# Vector_XY_Driver.net
KiCad netlist of a schematic drawn in EAGLE
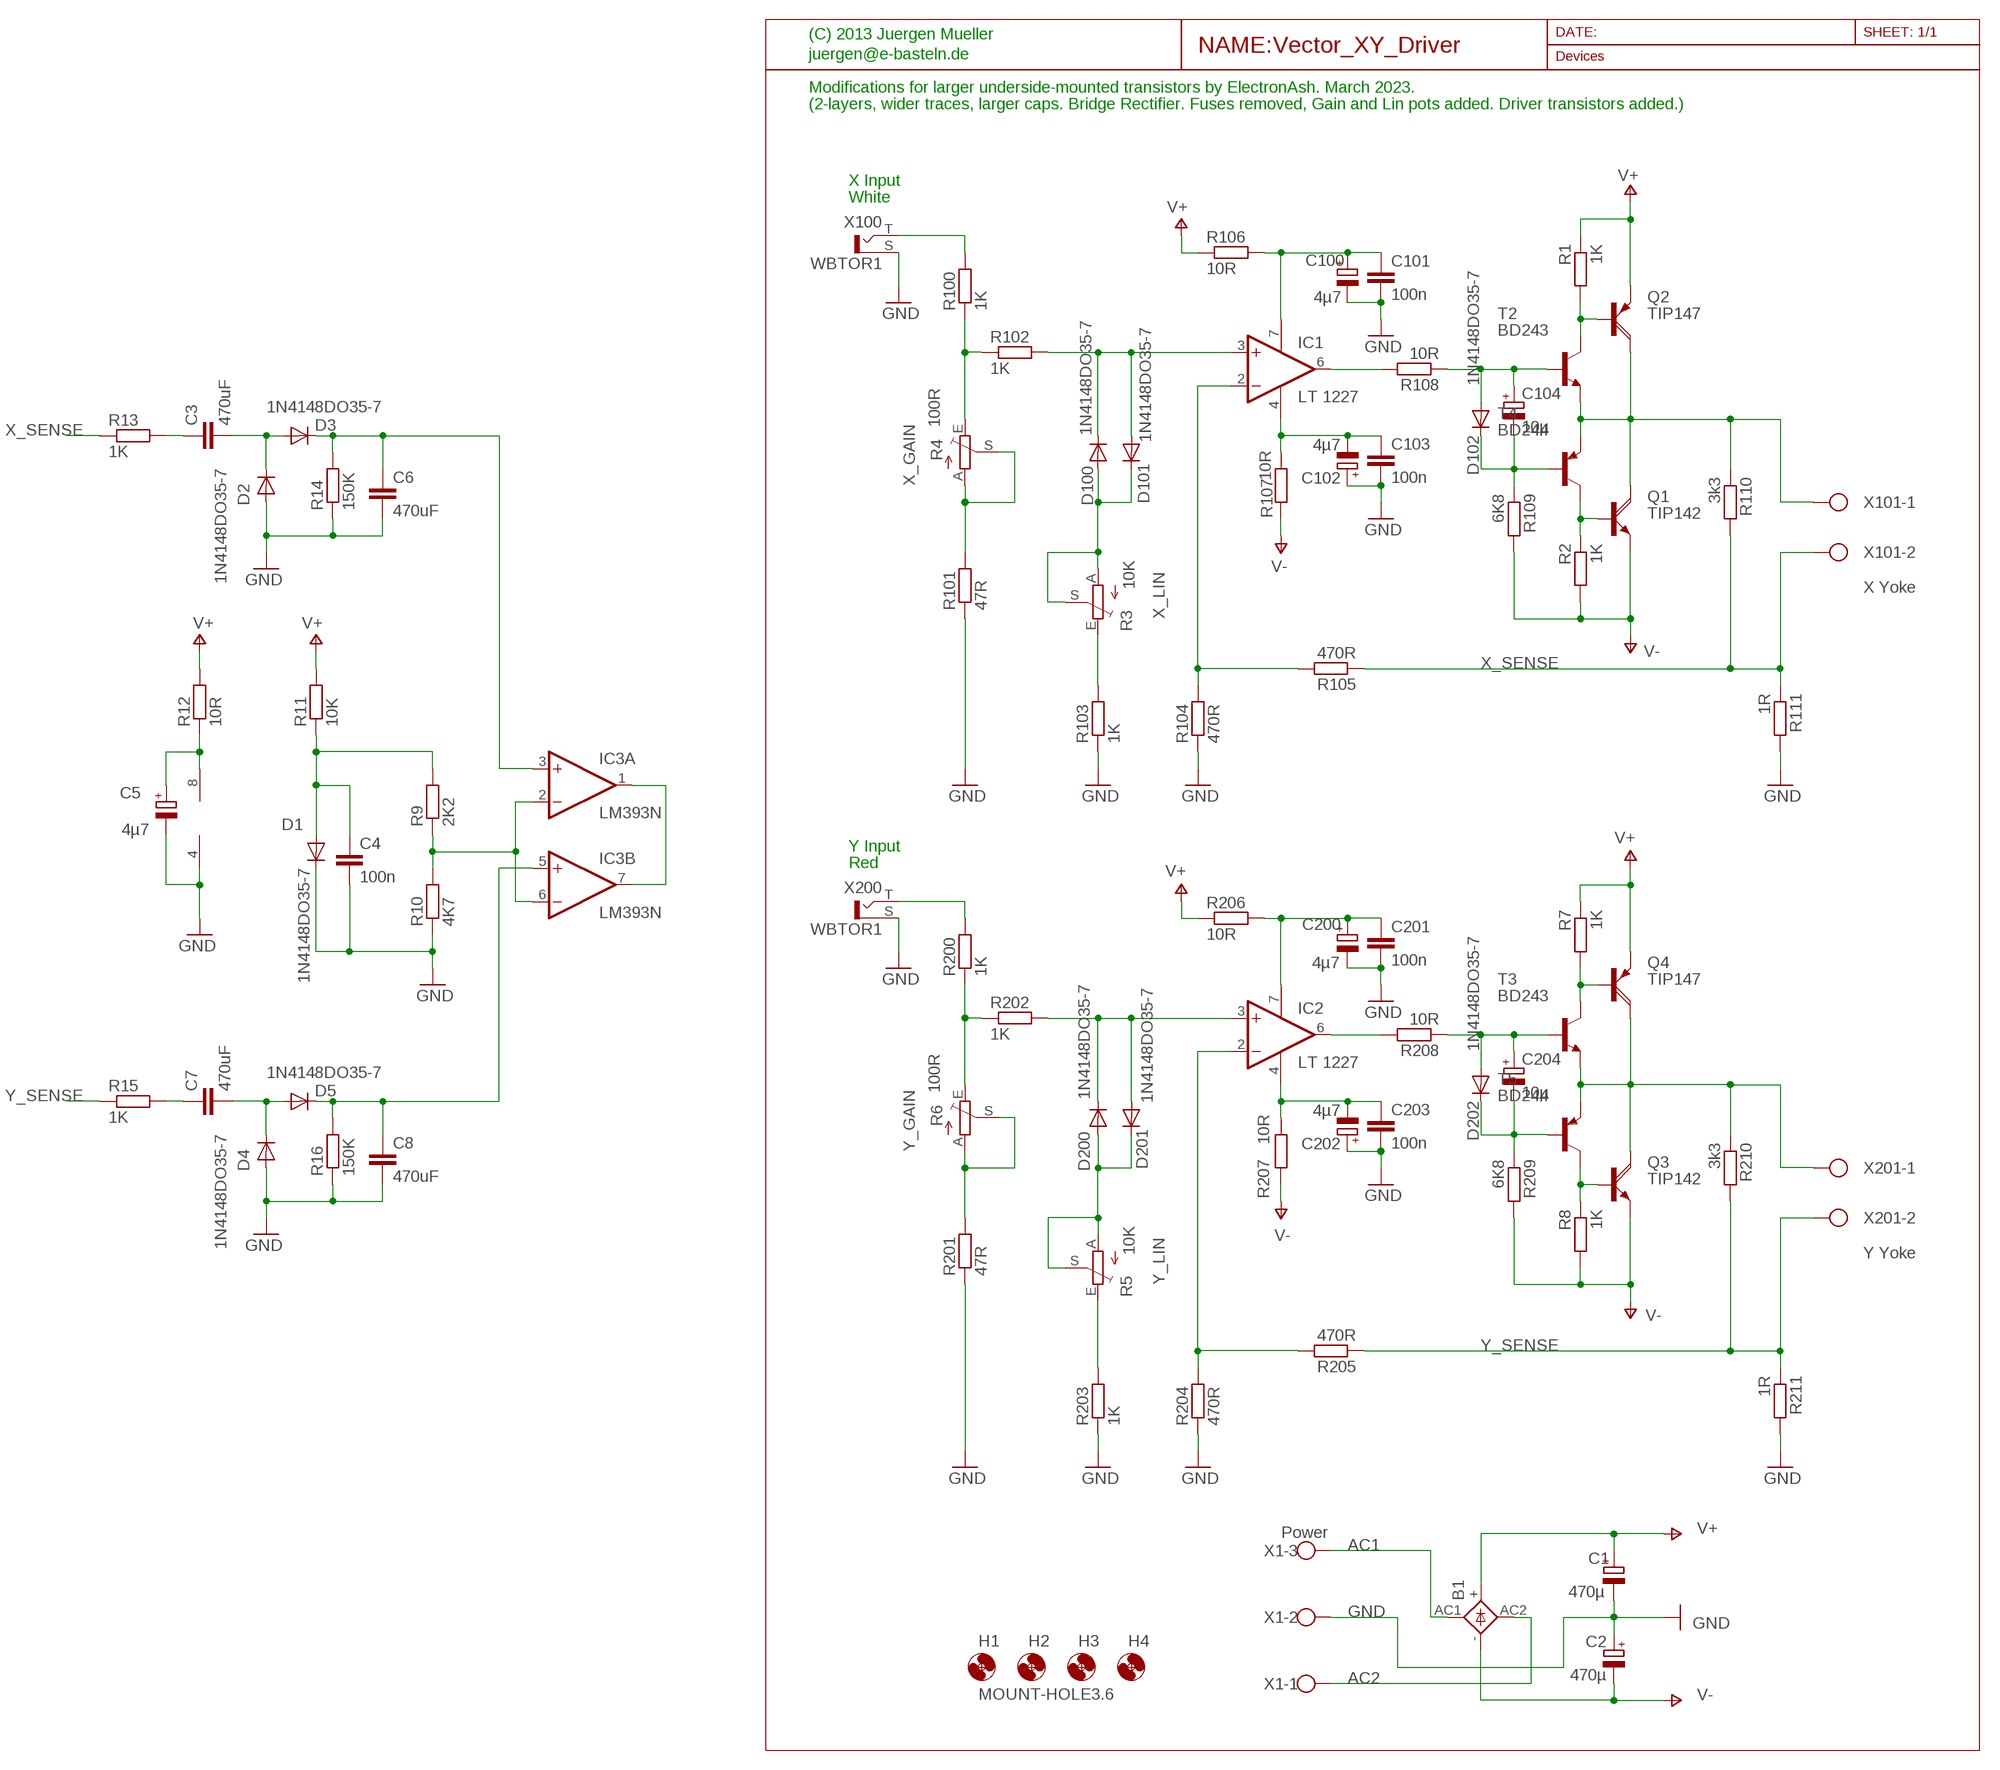
[diagram p0: schematic, sheet 1]

(export (version "E")
  (design (tool "Eeschema 10.0.6"))
  (components
    (comp (ref "B1")
      (value "2KBP")
      (footprint "eagle-import:2KBP")
      (libsource (lib "eagle-import") (part "2KBP"))
    )
    (comp (ref "C1")
      (value "470µ")
      (footprint "eagle-import:E7,5-16")
      (libsource (lib "eagle-import") (part "CPOL-EUE7.5-16"))
    )
    (comp (ref "C2")
      (value "470µ")
      (footprint "eagle-import:E7,5-16")
      (libsource (lib "eagle-import") (part "CPOL-EUE7.5-16"))
    )
    (comp (ref "C3")
      (value "470uF")
      (footprint "eagle-import:C025_050-025X075")
      (libsource (lib "eagle-import") (part "C-EU025_050-025X075"))
    )
    (comp (ref "C4")
      (value "100n")
      (footprint "eagle-import:C025_050-025X075")
      (libsource (lib "eagle-import") (part "C-EU025_050-025X075"))
    )
    (comp (ref "C5")
      (value "4µ7")
      (footprint "eagle-import:E2,5-6")
      (libsource (lib "eagle-import") (part "CPOL-EUE2.5-6"))
    )
    (comp (ref "C6")
      (value "470uF")
      (footprint "eagle-import:C025_050-025X075")
      (libsource (lib "eagle-import") (part "C-EU025_050-025X075"))
    )
    (comp (ref "C7")
      (value "470uF")
      (footprint "eagle-import:C025_050-025X075")
      (libsource (lib "eagle-import") (part "C-EU025_050-025X075"))
    )
    (comp (ref "C8")
      (value "470uF")
      (footprint "eagle-import:C025_050-025X075")
      (libsource (lib "eagle-import") (part "C-EU025_050-025X075"))
    )
    (comp (ref "C100")
      (value "4µ7")
      (footprint "eagle-import:E2,5-6")
      (libsource (lib "eagle-import") (part "CPOL-EUE2.5-6"))
    )
    (comp (ref "C101")
      (value "100n")
      (footprint "eagle-import:C025_050-025X075")
      (libsource (lib "eagle-import") (part "C-EU025_050-025X075"))
    )
    (comp (ref "C102")
      (value "4µ7")
      (footprint "eagle-import:E2,5-6")
      (libsource (lib "eagle-import") (part "CPOL-EUE2.5-6"))
    )
    (comp (ref "C103")
      (value "100n")
      (footprint "eagle-import:C025_050-025X075")
      (libsource (lib "eagle-import") (part "C-EU025_050-025X075"))
    )
    (comp (ref "C104")
      (value "10µ")
      (footprint "eagle-import:E15-5")
      (libsource (lib "eagle-import") (part "CPOL-EUE15-5AXIAL"))
    )
    (comp (ref "C200")
      (value "4µ7")
      (footprint "eagle-import:E2,5-6")
      (libsource (lib "eagle-import") (part "CPOL-EUE2.5-6"))
    )
    (comp (ref "C201")
      (value "100n")
      (footprint "eagle-import:C025_050-025X075")
      (libsource (lib "eagle-import") (part "C-EU025_050-025X075"))
    )
    (comp (ref "C202")
      (value "4µ7")
      (footprint "eagle-import:E2,5-6")
      (libsource (lib "eagle-import") (part "CPOL-EUE2.5-6"))
    )
    (comp (ref "C203")
      (value "100n")
      (footprint "eagle-import:C025_050-025X075")
      (libsource (lib "eagle-import") (part "C-EU025_050-025X075"))
    )
    (comp (ref "C204")
      (value "10µ")
      (footprint "eagle-import:E15-5")
      (libsource (lib "eagle-import") (part "CPOL-EUE15-5AXIAL"))
    )
    (comp (ref "D1")
      (value "1N4148DO35-7")
      (footprint "eagle-import:DO35-7")
      (libsource (lib "eagle-import") (part "1N4148DO35-7"))
    )
    (comp (ref "D2")
      (value "1N4148DO35-7")
      (footprint "eagle-import:DO35-7")
      (libsource (lib "eagle-import") (part "1N4148DO35-7"))
    )
    (comp (ref "D3")
      (value "1N4148DO35-7")
      (footprint "eagle-import:DO35-7")
      (libsource (lib "eagle-import") (part "1N4148DO35-7"))
    )
    (comp (ref "D4")
      (value "1N4148DO35-7")
      (footprint "eagle-import:DO35-7")
      (libsource (lib "eagle-import") (part "1N4148DO35-7"))
    )
    (comp (ref "D5")
      (value "1N4148DO35-7")
      (footprint "eagle-import:DO35-7")
      (libsource (lib "eagle-import") (part "1N4148DO35-7"))
    )
    (comp (ref "D100")
      (value "1N4148DO35-7")
      (footprint "eagle-import:DO35-7")
      (libsource (lib "eagle-import") (part "1N4148DO35-7"))
    )
    (comp (ref "D101")
      (value "1N4148DO35-7")
      (footprint "eagle-import:DO35-7")
      (libsource (lib "eagle-import") (part "1N4148DO35-7"))
    )
    (comp (ref "D102")
      (value "1N4148DO35-7")
      (footprint "eagle-import:DO35-7")
      (libsource (lib "eagle-import") (part "1N4148DO35-7"))
    )
    (comp (ref "D200")
      (value "1N4148DO35-7")
      (footprint "eagle-import:DO35-7")
      (libsource (lib "eagle-import") (part "1N4148DO35-7"))
    )
    (comp (ref "D201")
      (value "1N4148DO35-7")
      (footprint "eagle-import:DO35-7")
      (libsource (lib "eagle-import") (part "1N4148DO35-7"))
    )
    (comp (ref "D202")
      (value "1N4148DO35-7")
      (footprint "eagle-import:DO35-7")
      (libsource (lib "eagle-import") (part "1N4148DO35-7"))
    )
    (comp (ref "H1")
      (value "MOUNT-HOLE3.6")
      (footprint "eagle-import:3,6")
      (libsource (lib "eagle-import") (part "MOUNT-HOLE3.6"))
    )
    (comp (ref "H2")
      (value "MOUNT-HOLE3.6")
      (footprint "eagle-import:3,6")
      (libsource (lib "eagle-import") (part "MOUNT-HOLE3.6"))
    )
    (comp (ref "H3")
      (value "MOUNT-HOLE3.6")
      (footprint "eagle-import:3,6")
      (libsource (lib "eagle-import") (part "MOUNT-HOLE3.6"))
    )
    (comp (ref "H4")
      (value "MOUNT-HOLE3.6")
      (footprint "eagle-import:3,6")
      (libsource (lib "eagle-import") (part "MOUNT-HOLE3.6"))
    )
    (comp (ref "IC1")
      (value "LT 1227")
      (footprint "eagle-import:DIL08")
      (libsource (lib "eagle-import") (part "1AMP_P7+4N"))
    )
    (comp (ref "IC2")
      (value "LT 1227")
      (footprint "eagle-import:DIL08")
      (libsource (lib "eagle-import") (part "1AMP_P7+4N"))
    )
    (comp (ref "IC3")
      (value "LM393N")
      (footprint "eagle-import:DIL08")
      (libsource (lib "eagle-import") (part "LM393N"))
    )
    (comp (ref "Q1")
      (value "TIP142")
      (footprint "eagle-import:SOT93")
      (libsource (lib "eagle-import") (part "TIP142"))
    )
    (comp (ref "Q2")
      (value "TIP147")
      (footprint "eagle-import:SOT93")
      (libsource (lib "eagle-import") (part "TIP147"))
    )
    (comp (ref "Q3")
      (value "TIP142")
      (footprint "eagle-import:SOT93")
      (libsource (lib "eagle-import") (part "TIP142"))
    )
    (comp (ref "Q4")
      (value "TIP147")
      (footprint "eagle-import:SOT93")
      (libsource (lib "eagle-import") (part "TIP147"))
    )
    (comp (ref "R1")
      (value "1K")
      (footprint "eagle-import:0207_10")
      (libsource (lib "eagle-import") (part "R-EU_0207/10"))
    )
    (comp (ref "R2")
      (value "1K")
      (footprint "eagle-import:0207_10")
      (libsource (lib "eagle-import") (part "R-EU_0207/10"))
    )
    (comp (ref "R3")
      (value "10K")
      (footprint "eagle-import:B25P")
      (libsource (lib "eagle-import") (part "TRIM_EU-B25P"))
    )
    (comp (ref "R4")
      (value "100R")
      (footprint "eagle-import:B25P")
      (libsource (lib "eagle-import") (part "TRIM_EU-B25P"))
    )
    (comp (ref "R5")
      (value "10K")
      (footprint "eagle-import:B25P")
      (libsource (lib "eagle-import") (part "TRIM_EU-B25P"))
    )
    (comp (ref "R6")
      (value "100R")
      (footprint "eagle-import:B25P")
      (libsource (lib "eagle-import") (part "TRIM_EU-B25P"))
    )
    (comp (ref "R7")
      (value "1K")
      (footprint "eagle-import:0207_10")
      (libsource (lib "eagle-import") (part "R-EU_0207/10"))
    )
    (comp (ref "R8")
      (value "1K")
      (footprint "eagle-import:0207_10")
      (libsource (lib "eagle-import") (part "R-EU_0207/10"))
    )
    (comp (ref "R9")
      (value "2K2")
      (footprint "eagle-import:0207_10")
      (libsource (lib "eagle-import") (part "R-EU_0207/10"))
    )
    (comp (ref "R10")
      (value "4K7")
      (footprint "eagle-import:0207_10")
      (libsource (lib "eagle-import") (part "R-EU_0207/10"))
    )
    (comp (ref "R11")
      (value "10K")
      (footprint "eagle-import:0207_10")
      (libsource (lib "eagle-import") (part "R-EU_0207/10"))
    )
    (comp (ref "R12")
      (value "10R")
      (footprint "eagle-import:0207_10")
      (libsource (lib "eagle-import") (part "R-EU_0207/10"))
    )
    (comp (ref "R13")
      (value "1K")
      (footprint "eagle-import:0207_10")
      (libsource (lib "eagle-import") (part "R-EU_0207/10"))
    )
    (comp (ref "R14")
      (value "150K")
      (footprint "eagle-import:0207_10")
      (libsource (lib "eagle-import") (part "R-EU_0207/10"))
    )
    (comp (ref "R15")
      (value "1K")
      (footprint "eagle-import:0207_10")
      (libsource (lib "eagle-import") (part "R-EU_0207/10"))
    )
    (comp (ref "R16")
      (value "150K")
      (footprint "eagle-import:0207_10")
      (libsource (lib "eagle-import") (part "R-EU_0207/10"))
    )
    (comp (ref "R100")
      (value "1K")
      (footprint "eagle-import:0207_10")
      (libsource (lib "eagle-import") (part "R-EU_0207/10"))
    )
    (comp (ref "R101")
      (value "47R")
      (footprint "eagle-import:0207_10")
      (libsource (lib "eagle-import") (part "R-EU_0207/10"))
    )
    (comp (ref "R102")
      (value "1K")
      (footprint "eagle-import:0207_10")
      (libsource (lib "eagle-import") (part "R-EU_0207/10"))
    )
    (comp (ref "R103")
      (value "1K")
      (footprint "eagle-import:0207_10")
      (libsource (lib "eagle-import") (part "R-EU_0207/10"))
    )
    (comp (ref "R104")
      (value "470R")
      (footprint "eagle-import:0207_10")
      (libsource (lib "eagle-import") (part "R-EU_0207/10"))
    )
    (comp (ref "R105")
      (value "470R")
      (footprint "eagle-import:0207_10")
      (libsource (lib "eagle-import") (part "R-EU_0207/10"))
    )
    (comp (ref "R106")
      (value "10R")
      (footprint "eagle-import:0207_12")
      (libsource (lib "eagle-import") (part "R-EU_0207/12"))
    )
    (comp (ref "R107")
      (value "10R")
      (footprint "eagle-import:0207_12")
      (libsource (lib "eagle-import") (part "R-EU_0207/12"))
    )
    (comp (ref "R108")
      (value "10R")
      (footprint "eagle-import:0207_12")
      (libsource (lib "eagle-import") (part "R-EU_0207/12"))
    )
    (comp (ref "R109")
      (value "6K8")
      (footprint "eagle-import:0207_10")
      (libsource (lib "eagle-import") (part "R-EU_0207/10"))
    )
    (comp (ref "R110")
      (value "3k3")
      (footprint "eagle-import:0207_10")
      (libsource (lib "eagle-import") (part "R-EU_0207/10"))
    )
    (comp (ref "R111")
      (value "1R")
      (footprint "eagle-import:0617_17")
      (libsource (lib "eagle-import") (part "R-EU_0617/17"))
    )
    (comp (ref "R200")
      (value "1K")
      (footprint "eagle-import:0207_10")
      (libsource (lib "eagle-import") (part "R-EU_0207/10"))
    )
    (comp (ref "R201")
      (value "47R")
      (footprint "eagle-import:0207_10")
      (libsource (lib "eagle-import") (part "R-EU_0207/10"))
    )
    (comp (ref "R202")
      (value "1K")
      (footprint "eagle-import:0207_10")
      (libsource (lib "eagle-import") (part "R-EU_0207/10"))
    )
    (comp (ref "R203")
      (value "1K")
      (footprint "eagle-import:0207_10")
      (libsource (lib "eagle-import") (part "R-EU_0207/10"))
    )
    (comp (ref "R204")
      (value "470R")
      (footprint "eagle-import:0207_10")
      (libsource (lib "eagle-import") (part "R-EU_0207/10"))
    )
    (comp (ref "R205")
      (value "470R")
      (footprint "eagle-import:0207_10")
      (libsource (lib "eagle-import") (part "R-EU_0207/10"))
    )
    (comp (ref "R206")
      (value "10R")
      (footprint "eagle-import:0207_12")
      (libsource (lib "eagle-import") (part "R-EU_0207/12"))
    )
    (comp (ref "R207")
      (value "10R")
      (footprint "eagle-import:0207_12")
      (libsource (lib "eagle-import") (part "R-EU_0207/12"))
    )
    (comp (ref "R208")
      (value "10R")
      (footprint "eagle-import:0207_12")
      (libsource (lib "eagle-import") (part "R-EU_0207/12"))
    )
    (comp (ref "R209")
      (value "6K8")
      (footprint "eagle-import:0207_10")
      (libsource (lib "eagle-import") (part "R-EU_0207/10"))
    )
    (comp (ref "R210")
      (value "3k3")
      (footprint "eagle-import:0207_10")
      (libsource (lib "eagle-import") (part "R-EU_0207/10"))
    )
    (comp (ref "R211")
      (value "1R")
      (footprint "eagle-import:0617_17")
      (libsource (lib "eagle-import") (part "R-EU_0617/17"))
    )
    (comp (ref "T2")
      (value "BD243")
      (footprint "eagle-import:TO220")
      (libsource (lib "eagle-import") (part "BD243"))
    )
    (comp (ref "T3")
      (value "BD243")
      (footprint "eagle-import:TO220")
      (libsource (lib "eagle-import") (part "BD243"))
    )
    (comp (ref "T4")
      (value "BD244")
      (footprint "eagle-import:TO220")
      (libsource (lib "eagle-import") (part "BD244"))
    )
    (comp (ref "T5")
      (value "BD244")
      (footprint "eagle-import:TO220")
      (libsource (lib "eagle-import") (part "BD244"))
    )
    (comp (ref "X1")
      (value "Power")
      (footprint "eagle-import:W237-103")
      (fields (field (name "MPN") "237-103"))
      (libsource (lib "eagle-import") (part "W237-103"))
    )
    (comp (ref "X100")
      (value "WBTOR1")
      (footprint "eagle-import:WBTOR1")
      (fields (field (name "MPN") "WBTOR 1 BLACK"))
      (libsource (lib "eagle-import") (part "WBTOR1"))
    )
    (comp (ref "X101")
      (value "X Yoke")
      (footprint "eagle-import:W237-102")
      (fields (field (name "MPN") "237-102"))
      (libsource (lib "eagle-import") (part "W237-102"))
    )
    (comp (ref "X200")
      (value "WBTOR1")
      (footprint "eagle-import:WBTOR1")
      (fields (field (name "MPN") "WBTOR 1 BLACK"))
      (libsource (lib "eagle-import") (part "WBTOR1"))
    )
    (comp (ref "X201")
      (value "Y Yoke")
      (footprint "eagle-import:W237-102")
      (fields (field (name "MPN") "237-102"))
      (libsource (lib "eagle-import") (part "W237-102"))
    )
  )
  (nets
    (net (code "1") (name "/AC1") (class "Default")
      (node (ref "B1") (pin "AC1") (pinfunction "AC1_AC1") (pintype "passive"))
      (node (ref "X1") (pin "3") (pinfunction "KL_3") (pintype "passive"))
    )
    (net (code "2") (name "/AC2") (class "Default")
      (node (ref "B1") (pin "AC2") (pinfunction "AC2_AC2") (pintype "passive"))
      (node (ref "X1") (pin "1") (pinfunction "KL_1") (pintype "passive"))
    )
    (net (code "3") (name "/X_SENSE") (class "Default")
      (node (ref "R105") (pin "1") (pinfunction "1_1") (pintype "passive"))
      (node (ref "R110") (pin "2") (pinfunction "2_2") (pintype "passive"))
      (node (ref "R111") (pin "1") (pinfunction "1_1") (pintype "passive"))
      (node (ref "R13") (pin "1") (pinfunction "1_1") (pintype "passive"))
      (node (ref "X101") (pin "2") (pinfunction "KL_2") (pintype "passive"))
    )
    (net (code "4") (name "/Y_SENSE") (class "Default")
      (node (ref "R15") (pin "1") (pinfunction "1_1") (pintype "passive"))
      (node (ref "R205") (pin "1") (pinfunction "1_1") (pintype "passive"))
      (node (ref "R210") (pin "2") (pinfunction "2_2") (pintype "passive"))
      (node (ref "R211") (pin "1") (pinfunction "1_1") (pintype "passive"))
      (node (ref "X201") (pin "2") (pinfunction "KL_2") (pintype "passive"))
    )
    (net (code "5") (name "GND") (class "Default")
      (node (ref "C1") (pin "-") (pinfunction "-_-") (pintype "passive"))
      (node (ref "C100") (pin "-") (pinfunction "-_-") (pintype "passive"))
      (node (ref "C101") (pin "2") (pinfunction "2_2") (pintype "passive"))
      (node (ref "C102") (pin "+") (pinfunction "+_+") (pintype "passive"))
      (node (ref "C103") (pin "2") (pinfunction "2_2") (pintype "passive"))
      (node (ref "C2") (pin "+") (pinfunction "+_+") (pintype "passive"))
      (node (ref "C200") (pin "-") (pinfunction "-_-") (pintype "passive"))
      (node (ref "C201") (pin "2") (pinfunction "2_2") (pintype "passive"))
      (node (ref "C202") (pin "+") (pinfunction "+_+") (pintype "passive"))
      (node (ref "C203") (pin "2") (pinfunction "2_2") (pintype "passive"))
      (node (ref "C4") (pin "2") (pinfunction "2_2") (pintype "passive"))
      (node (ref "C5") (pin "-") (pinfunction "-_-") (pintype "passive"))
      (node (ref "C6") (pin "2") (pinfunction "2_2") (pintype "passive"))
      (node (ref "C8") (pin "2") (pinfunction "2_2") (pintype "passive"))
      (node (ref "D1") (pin "C") (pinfunction "C_C") (pintype "passive"))
      (node (ref "D2") (pin "A") (pinfunction "A_A") (pintype "passive"))
      (node (ref "D4") (pin "A") (pinfunction "A_A") (pintype "passive"))
      (node (ref "IC3") (pin "4") (pinfunction "V-_4") (pintype "power_in"))
      (node (ref "R10") (pin "1") (pinfunction "1_1") (pintype "passive"))
      (node (ref "R101") (pin "1") (pinfunction "1_1") (pintype "passive"))
      (node (ref "R103") (pin "1") (pinfunction "1_1") (pintype "passive"))
      (node (ref "R104") (pin "1") (pinfunction "1_1") (pintype "passive"))
      (node (ref "R111") (pin "2") (pinfunction "2_2") (pintype "passive"))
      (node (ref "R14") (pin "1") (pinfunction "1_1") (pintype "passive"))
      (node (ref "R16") (pin "1") (pinfunction "1_1") (pintype "passive"))
      (node (ref "R201") (pin "1") (pinfunction "1_1") (pintype "passive"))
      (node (ref "R203") (pin "1") (pinfunction "1_1") (pintype "passive"))
      (node (ref "R204") (pin "1") (pinfunction "1_1") (pintype "passive"))
      (node (ref "R211") (pin "2") (pinfunction "2_2") (pintype "passive"))
      (node (ref "X1") (pin "2") (pinfunction "KL_2") (pintype "passive"))
      (node (ref "X100") (pin "S") (pinfunction "S_S") (pintype "passive"))
      (node (ref "X200") (pin "S") (pinfunction "S_S") (pintype "passive"))
    )
    (net (code "6") (name "Net-(C3-Pad1)") (class "Default")
      (node (ref "C3") (pin "1") (pinfunction "1_1") (pintype "passive"))
      (node (ref "R13") (pin "2") (pinfunction "2_2") (pintype "passive"))
    )
    (net (code "7") (name "Net-(C3-Pad2)") (class "Default")
      (node (ref "C3") (pin "2") (pinfunction "2_2") (pintype "passive"))
      (node (ref "D2") (pin "C") (pinfunction "C_C") (pintype "passive"))
      (node (ref "D3") (pin "A") (pinfunction "A_A") (pintype "passive"))
    )
    (net (code "8") (name "Net-(C4-Pad1)") (class "Default")
      (node (ref "C4") (pin "1") (pinfunction "1_1") (pintype "passive"))
      (node (ref "D1") (pin "A") (pinfunction "A_A") (pintype "passive"))
      (node (ref "R11") (pin "1") (pinfunction "1_1") (pintype "passive"))
      (node (ref "R9") (pin "2") (pinfunction "2_2") (pintype "passive"))
    )
    (net (code "9") (name "Net-(C7-Pad1)") (class "Default")
      (node (ref "C7") (pin "1") (pinfunction "1_1") (pintype "passive"))
      (node (ref "R15") (pin "2") (pinfunction "2_2") (pintype "passive"))
    )
    (net (code "10") (name "Net-(C7-Pad2)") (class "Default")
      (node (ref "C7") (pin "2") (pinfunction "2_2") (pintype "passive"))
      (node (ref "D4") (pin "C") (pinfunction "C_C") (pintype "passive"))
      (node (ref "D5") (pin "A") (pinfunction "A_A") (pintype "passive"))
    )
    (net (code "11") (name "Net-(D100-PadA)") (class "Default")
      (node (ref "D100") (pin "A") (pinfunction "A_A") (pintype "passive"))
      (node (ref "D101") (pin "C") (pinfunction "C_C") (pintype "passive"))
      (node (ref "R3") (pin "A") (pinfunction "A_A") (pintype "passive"))
      (node (ref "R3") (pin "S") (pinfunction "S_S") (pintype "passive"))
    )
    (net (code "12") (name "Net-(D200-PadA)") (class "Default")
      (node (ref "D200") (pin "A") (pinfunction "A_A") (pintype "passive"))
      (node (ref "D201") (pin "C") (pinfunction "C_C") (pintype "passive"))
      (node (ref "R5") (pin "A") (pinfunction "A_A") (pintype "passive"))
      (node (ref "R5") (pin "S") (pinfunction "S_S") (pintype "passive"))
    )
    (net (code "13") (name "Net-(IC1-+IN)") (class "Default")
      (node (ref "D100") (pin "C") (pinfunction "C_C") (pintype "passive"))
      (node (ref "D101") (pin "A") (pinfunction "A_A") (pintype "passive"))
      (node (ref "IC1") (pin "3") (pinfunction "+IN_3") (pintype "input"))
      (node (ref "R102") (pin "2") (pinfunction "2_2") (pintype "passive"))
    )
    (net (code "14") (name "Net-(IC1--IN)") (class "Default")
      (node (ref "IC1") (pin "2") (pinfunction "-IN_2") (pintype "input"))
      (node (ref "R104") (pin "2") (pinfunction "2_2") (pintype "passive"))
      (node (ref "R105") (pin "2") (pinfunction "2_2") (pintype "passive"))
    )
    (net (code "15") (name "Net-(IC1-OUT)") (class "Default")
      (node (ref "IC1") (pin "6") (pinfunction "OUT_6") (pintype "output"))
      (node (ref "R108") (pin "2") (pinfunction "2_2") (pintype "passive"))
    )
    (net (code "16") (name "Net-(IC1-V+)") (class "Default")
      (node (ref "C100") (pin "+") (pinfunction "+_+") (pintype "passive"))
      (node (ref "C101") (pin "1") (pinfunction "1_1") (pintype "passive"))
      (node (ref "IC1") (pin "7") (pinfunction "V+_7") (pintype "power_in"))
      (node (ref "R106") (pin "2") (pinfunction "2_2") (pintype "passive"))
    )
    (net (code "17") (name "Net-(IC1-V-)") (class "Default")
      (node (ref "C102") (pin "-") (pinfunction "-_-") (pintype "passive"))
      (node (ref "C103") (pin "1") (pinfunction "1_1") (pintype "passive"))
      (node (ref "IC1") (pin "4") (pinfunction "V-_4") (pintype "power_in"))
      (node (ref "R107") (pin "1") (pinfunction "1_1") (pintype "passive"))
    )
    (net (code "18") (name "Net-(IC2-+IN)") (class "Default")
      (node (ref "D200") (pin "C") (pinfunction "C_C") (pintype "passive"))
      (node (ref "D201") (pin "A") (pinfunction "A_A") (pintype "passive"))
      (node (ref "IC2") (pin "3") (pinfunction "+IN_3") (pintype "input"))
      (node (ref "R202") (pin "2") (pinfunction "2_2") (pintype "passive"))
    )
    (net (code "19") (name "Net-(IC2--IN)") (class "Default")
      (node (ref "IC2") (pin "2") (pinfunction "-IN_2") (pintype "input"))
      (node (ref "R204") (pin "2") (pinfunction "2_2") (pintype "passive"))
      (node (ref "R205") (pin "2") (pinfunction "2_2") (pintype "passive"))
    )
    (net (code "20") (name "Net-(IC2-OUT)") (class "Default")
      (node (ref "IC2") (pin "6") (pinfunction "OUT_6") (pintype "output"))
      (node (ref "R208") (pin "2") (pinfunction "2_2") (pintype "passive"))
    )
    (net (code "21") (name "Net-(IC2-V+)") (class "Default")
      (node (ref "C200") (pin "+") (pinfunction "+_+") (pintype "passive"))
      (node (ref "C201") (pin "1") (pinfunction "1_1") (pintype "passive"))
      (node (ref "IC2") (pin "7") (pinfunction "V+_7") (pintype "power_in"))
      (node (ref "R206") (pin "2") (pinfunction "2_2") (pintype "passive"))
    )
    (net (code "22") (name "Net-(IC2-V-)") (class "Default")
      (node (ref "C202") (pin "-") (pinfunction "-_-") (pintype "passive"))
      (node (ref "C203") (pin "1") (pinfunction "1_1") (pintype "passive"))
      (node (ref "IC2") (pin "4") (pinfunction "V-_4") (pintype "power_in"))
      (node (ref "R207") (pin "1") (pinfunction "1_1") (pintype "passive"))
    )
    (net (code "23") (name "Net-(IC3A-+IN)") (class "Default")
      (node (ref "C6") (pin "1") (pinfunction "1_1") (pintype "passive"))
      (node (ref "D3") (pin "C") (pinfunction "C_C") (pintype "passive"))
      (node (ref "IC3") (pin "3") (pinfunction "+IN_3") (pintype "input"))
      (node (ref "R14") (pin "2") (pinfunction "2_2") (pintype "passive"))
    )
    (net (code "24") (name "Net-(IC3A--IN)") (class "Default")
      (node (ref "IC3") (pin "2") (pinfunction "-IN_2") (pintype "input"))
      (node (ref "IC3") (pin "6") (pinfunction "-IN_6") (pintype "input"))
      (node (ref "R10") (pin "2") (pinfunction "2_2") (pintype "passive"))
      (node (ref "R9") (pin "1") (pinfunction "1_1") (pintype "passive"))
    )
    (net (code "25") (name "Net-(IC3A-OUT)") (class "Default")
      (node (ref "IC3") (pin "1") (pinfunction "OUT_1") (pintype "output"))
      (node (ref "IC3") (pin "7") (pinfunction "OUT_7") (pintype "output"))
    )
    (net (code "26") (name "Net-(IC3B-+IN)") (class "Default")
      (node (ref "C8") (pin "1") (pinfunction "1_1") (pintype "passive"))
      (node (ref "D5") (pin "C") (pinfunction "C_C") (pintype "passive"))
      (node (ref "IC3") (pin "5") (pinfunction "+IN_5") (pintype "input"))
      (node (ref "R16") (pin "2") (pinfunction "2_2") (pintype "passive"))
    )
    (net (code "27") (name "Net-(IC3C-V+)") (class "Default")
      (node (ref "C5") (pin "+") (pinfunction "+_+") (pintype "passive"))
      (node (ref "IC3") (pin "8") (pinfunction "V+_8") (pintype "power_in"))
      (node (ref "R12") (pin "1") (pinfunction "1_1") (pintype "passive"))
    )
    (net (code "28") (name "Net-(R100-Pad1)") (class "Default")
      (node (ref "R100") (pin "1") (pinfunction "1_1") (pintype "passive"))
      (node (ref "R102") (pin "1") (pinfunction "1_1") (pintype "passive"))
      (node (ref "R4") (pin "E") (pinfunction "E_E") (pintype "passive"))
    )
    (net (code "29") (name "Net-(R100-Pad2)") (class "Default")
      (node (ref "R100") (pin "2") (pinfunction "2_2") (pintype "passive"))
      (node (ref "X100") (pin "T") (pinfunction "T_T") (pintype "passive"))
    )
    (net (code "30") (name "Net-(R101-Pad2)") (class "Default")
      (node (ref "R101") (pin "2") (pinfunction "2_2") (pintype "passive"))
      (node (ref "R4") (pin "A") (pinfunction "A_A") (pintype "passive"))
      (node (ref "R4") (pin "S") (pinfunction "S_S") (pintype "passive"))
    )
    (net (code "31") (name "Net-(R103-Pad2)") (class "Default")
      (node (ref "R103") (pin "2") (pinfunction "2_2") (pintype "passive"))
      (node (ref "R3") (pin "E") (pinfunction "E_E") (pintype "passive"))
    )
    (net (code "32") (name "Net-(R200-Pad1)") (class "Default")
      (node (ref "R200") (pin "1") (pinfunction "1_1") (pintype "passive"))
      (node (ref "R202") (pin "1") (pinfunction "1_1") (pintype "passive"))
      (node (ref "R6") (pin "E") (pinfunction "E_E") (pintype "passive"))
    )
    (net (code "33") (name "Net-(R200-Pad2)") (class "Default")
      (node (ref "R200") (pin "2") (pinfunction "2_2") (pintype "passive"))
      (node (ref "X200") (pin "T") (pinfunction "T_T") (pintype "passive"))
    )
    (net (code "34") (name "Net-(R201-Pad2)") (class "Default")
      (node (ref "R201") (pin "2") (pinfunction "2_2") (pintype "passive"))
      (node (ref "R6") (pin "A") (pinfunction "A_A") (pintype "passive"))
      (node (ref "R6") (pin "S") (pinfunction "S_S") (pintype "passive"))
    )
    (net (code "35") (name "Net-(R203-Pad2)") (class "Default")
      (node (ref "R203") (pin "2") (pinfunction "2_2") (pintype "passive"))
      (node (ref "R5") (pin "E") (pinfunction "E_E") (pintype "passive"))
    )
    (net (code "36") (name "Net-(T2-B)") (class "Default")
      (node (ref "C104") (pin "+") (pinfunction "+_+") (pintype "passive"))
      (node (ref "D102") (pin "A") (pinfunction "A_A") (pintype "passive"))
      (node (ref "R108") (pin "1") (pinfunction "1_1") (pintype "passive"))
      (node (ref "T2") (pin "1") (pinfunction "B_1") (pintype "passive"))
    )
    (net (code "37") (name "Net-(T2-C)") (class "Default")
      (node (ref "Q2") (pin "B") (pinfunction "B_B") (pintype "passive"))
      (node (ref "R1") (pin "2") (pinfunction "2_2") (pintype "passive"))
      (node (ref "T2") (pin "2") (pinfunction "C_2") (pintype "passive"))
    )
    (net (code "38") (name "Net-(T2-E)") (class "Default")
      (node (ref "Q1") (pin "C") (pinfunction "C_C") (pintype "passive"))
      (node (ref "Q2") (pin "C") (pinfunction "C_C") (pintype "passive"))
      (node (ref "R110") (pin "1") (pinfunction "1_1") (pintype "passive"))
      (node (ref "T2") (pin "3") (pinfunction "E_3") (pintype "passive"))
      (node (ref "T4") (pin "3") (pinfunction "E_3") (pintype "passive"))
      (node (ref "X101") (pin "1") (pinfunction "KL_1") (pintype "passive"))
    )
    (net (code "39") (name "Net-(T3-B)") (class "Default")
      (node (ref "C204") (pin "+") (pinfunction "+_+") (pintype "passive"))
      (node (ref "D202") (pin "A") (pinfunction "A_A") (pintype "passive"))
      (node (ref "R208") (pin "1") (pinfunction "1_1") (pintype "passive"))
      (node (ref "T3") (pin "1") (pinfunction "B_1") (pintype "passive"))
    )
    (net (code "40") (name "Net-(T3-C)") (class "Default")
      (node (ref "Q4") (pin "B") (pinfunction "B_B") (pintype "passive"))
      (node (ref "R7") (pin "2") (pinfunction "2_2") (pintype "passive"))
      (node (ref "T3") (pin "2") (pinfunction "C_2") (pintype "passive"))
    )
    (net (code "41") (name "Net-(T3-E)") (class "Default")
      (node (ref "Q3") (pin "C") (pinfunction "C_C") (pintype "passive"))
      (node (ref "Q4") (pin "C") (pinfunction "C_C") (pintype "passive"))
      (node (ref "R210") (pin "1") (pinfunction "1_1") (pintype "passive"))
      (node (ref "T3") (pin "3") (pinfunction "E_3") (pintype "passive"))
      (node (ref "T5") (pin "3") (pinfunction "E_3") (pintype "passive"))
      (node (ref "X201") (pin "1") (pinfunction "KL_1") (pintype "passive"))
    )
    (net (code "42") (name "Net-(T4-B)") (class "Default")
      (node (ref "C104") (pin "-") (pinfunction "-_-") (pintype "passive"))
      (node (ref "D102") (pin "C") (pinfunction "C_C") (pintype "passive"))
      (node (ref "R109") (pin "1") (pinfunction "1_1") (pintype "passive"))
      (node (ref "T4") (pin "1") (pinfunction "B_1") (pintype "passive"))
    )
    (net (code "43") (name "Net-(T4-C)") (class "Default")
      (node (ref "Q1") (pin "B") (pinfunction "B_B") (pintype "passive"))
      (node (ref "R2") (pin "1") (pinfunction "1_1") (pintype "passive"))
      (node (ref "T4") (pin "2") (pinfunction "C_2") (pintype "passive"))
    )
    (net (code "44") (name "Net-(T5-B)") (class "Default")
      (node (ref "C204") (pin "-") (pinfunction "-_-") (pintype "passive"))
      (node (ref "D202") (pin "C") (pinfunction "C_C") (pintype "passive"))
      (node (ref "R209") (pin "1") (pinfunction "1_1") (pintype "passive"))
      (node (ref "T5") (pin "1") (pinfunction "B_1") (pintype "passive"))
    )
    (net (code "45") (name "Net-(T5-C)") (class "Default")
      (node (ref "Q3") (pin "B") (pinfunction "B_B") (pintype "passive"))
      (node (ref "R8") (pin "1") (pinfunction "1_1") (pintype "passive"))
      (node (ref "T5") (pin "2") (pinfunction "C_2") (pintype "passive"))
    )
    (net (code "46") (name "V+") (class "Default")
      (node (ref "B1") (pin "+") (pinfunction "+_+") (pintype "passive"))
      (node (ref "C1") (pin "+") (pinfunction "+_+") (pintype "passive"))
      (node (ref "Q2") (pin "E") (pinfunction "E_E") (pintype "passive"))
      (node (ref "Q4") (pin "E") (pinfunction "E_E") (pintype "passive"))
      (node (ref "R1") (pin "1") (pinfunction "1_1") (pintype "passive"))
      (node (ref "R106") (pin "1") (pinfunction "1_1") (pintype "passive"))
      (node (ref "R11") (pin "2") (pinfunction "2_2") (pintype "passive"))
      (node (ref "R12") (pin "2") (pinfunction "2_2") (pintype "passive"))
      (node (ref "R206") (pin "1") (pinfunction "1_1") (pintype "passive"))
      (node (ref "R7") (pin "1") (pinfunction "1_1") (pintype "passive"))
    )
    (net (code "47") (name "V-") (class "Default")
      (node (ref "B1") (pin "-") (pinfunction "-_-") (pintype "passive"))
      (node (ref "C2") (pin "-") (pinfunction "-_-") (pintype "passive"))
      (node (ref "Q1") (pin "E") (pinfunction "E_E") (pintype "passive"))
      (node (ref "Q3") (pin "E") (pinfunction "E_E") (pintype "passive"))
      (node (ref "R107") (pin "2") (pinfunction "2_2") (pintype "passive"))
      (node (ref "R109") (pin "2") (pinfunction "2_2") (pintype "passive"))
      (node (ref "R2") (pin "2") (pinfunction "2_2") (pintype "passive"))
      (node (ref "R207") (pin "2") (pinfunction "2_2") (pintype "passive"))
      (node (ref "R209") (pin "2") (pinfunction "2_2") (pintype "passive"))
      (node (ref "R8") (pin "2") (pinfunction "2_2") (pintype "passive"))
    )
  )
)
